# RoboticArmIEEE_Main.net
KiCad netlist of a schematic drawn in Altium Designer
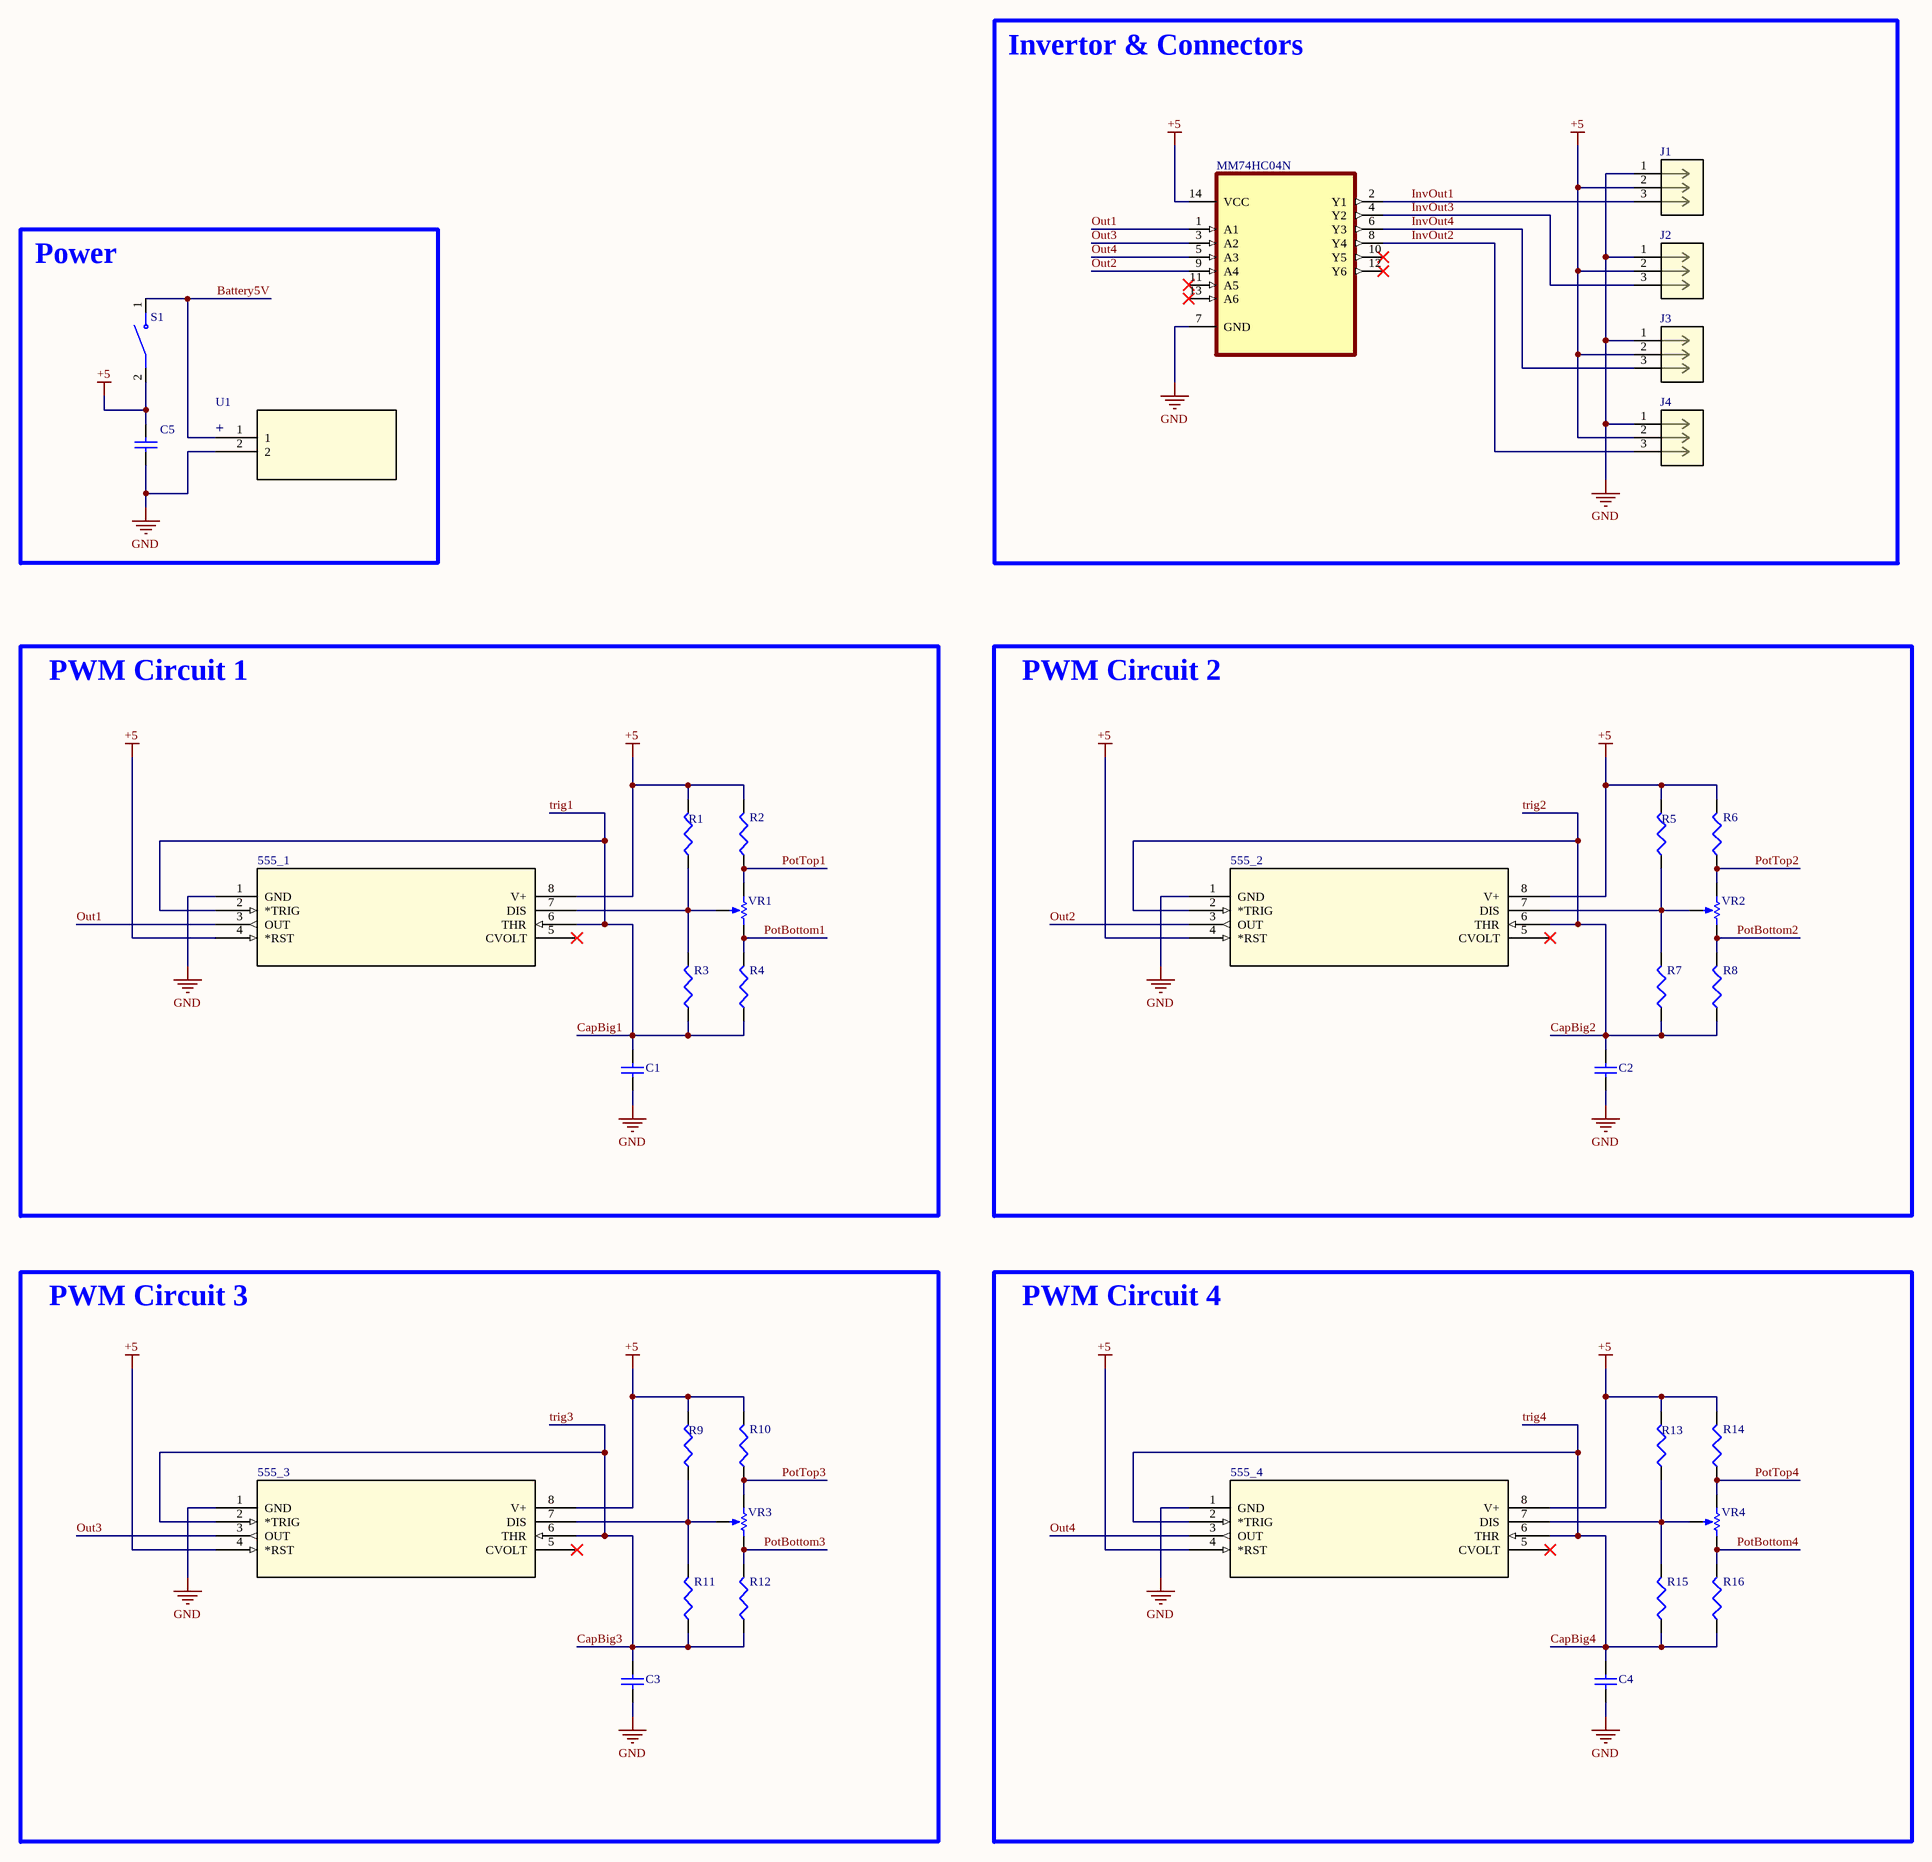
[diagram p0: RoboticArmIEEE_Main.SchDoc]

(export (version "E")
  (design (tool "Eeschema 10.0.6"))
  (components
    (comp (ref "555_1")
      (value "LMC555CNNOPB")
      (footprint "LMC555CNNOPB:N08E_TEX")
      (description "No Description Available")
      (libsource (lib "LMC555CNNOPB") (part "LMC555CNNOPB"))
    )
    (comp (ref "555_2")
      (value "LMC555CNNOPB")
      (footprint "LMC555CNNOPB:N08E_TEX")
      (description "No Description Available")
      (libsource (lib "LMC555CNNOPB") (part "LMC555CNNOPB"))
    )
    (comp (ref "555_3")
      (value "LMC555CNNOPB")
      (footprint "LMC555CNNOPB:N08E_TEX")
      (description "No Description Available")
      (libsource (lib "LMC555CNNOPB") (part "LMC555CNNOPB"))
    )
    (comp (ref "555_4")
      (value "LMC555CNNOPB")
      (footprint "LMC555CNNOPB:N08E_TEX")
      (description "No Description Available")
      (libsource (lib "LMC555CNNOPB") (part "LMC555CNNOPB"))
    )
    (comp (ref "C1")
      (value "Cap_Big")
      (footprint "Cap_Big")
      (libsource (lib "RoboticArmIEEE_SCHLib") (part "Cap_Big"))
    )
    (comp (ref "C2")
      (value "Cap_Big")
      (footprint "Cap_Big")
      (libsource (lib "RoboticArmIEEE_SCHLib") (part "Cap_Big"))
    )
    (comp (ref "C3")
      (value "Cap_Big")
      (footprint "Cap_Big")
      (libsource (lib "RoboticArmIEEE_SCHLib") (part "Cap_Big"))
    )
    (comp (ref "C4")
      (value "Cap_Big")
      (footprint "Cap_Big")
      (libsource (lib "RoboticArmIEEE_SCHLib") (part "Cap_Big"))
    )
    (comp (ref "C5")
      (value "Cap_Small")
      (footprint "RoboticArmIEEE_PCBLib:Cap_Small")
      (libsource (lib "RoboticArmIEEE_SCHLib") (part "Cap_Small"))
    )
    (comp (ref "J1")
      (value "PPTC031LFBN-RC")
      (footprint "PPTC031LFBN-RC:CONN_PPTC031_SUL")
      (description "No Description Available")
      (libsource (lib "PPTC031LFBN-RC") (part "PPTC031LFBN-RC"))
    )
    (comp (ref "J2")
      (value "PPTC031LFBN-RC")
      (footprint "PPTC031LFBN-RC:CONN_PPTC031_SUL")
      (description "No Description Available")
      (libsource (lib "PPTC031LFBN-RC") (part "PPTC031LFBN-RC"))
    )
    (comp (ref "J3")
      (value "PPTC031LFBN-RC")
      (footprint "PPTC031LFBN-RC:CONN_PPTC031_SUL")
      (description "No Description Available")
      (libsource (lib "PPTC031LFBN-RC") (part "PPTC031LFBN-RC"))
    )
    (comp (ref "J4")
      (value "PPTC031LFBN-RC")
      (footprint "PPTC031LFBN-RC:CONN_PPTC031_SUL")
      (description "No Description Available")
      (libsource (lib "PPTC031LFBN-RC") (part "PPTC031LFBN-RC"))
    )
    (comp (ref "MM74HC04N")
      (value "MM74HC04N")
      (footprint "DIP254P762X533-14")
      (description "Inverter IC 6 Channel 14-PDIP")
      (fields (field (name "MF") "ON Semiconductor"))
      (libsource (lib "Leon Engle") (part "MM74HC04N"))
    )
    (comp (ref "R1")
      (value "R?")
      (footprint "Resistor")
      (libsource (lib "RoboticArmIEEE_SCHLib") (part "Resistor"))
    )
    (comp (ref "R2")
      (value "Resistor")
      (footprint "Resistor")
      (libsource (lib "RoboticArmIEEE_SCHLib") (part "Resistor"))
    )
    (comp (ref "R3")
      (value "Resistor")
      (footprint "Resistor")
      (libsource (lib "RoboticArmIEEE_SCHLib") (part "Resistor"))
    )
    (comp (ref "R4")
      (value "Resistor")
      (footprint "Resistor")
      (libsource (lib "RoboticArmIEEE_SCHLib") (part "Resistor"))
    )
    (comp (ref "R5")
      (value "R?")
      (footprint "Resistor")
      (libsource (lib "RoboticArmIEEE_SCHLib") (part "Resistor"))
    )
    (comp (ref "R6")
      (value "Resistor")
      (footprint "Resistor")
      (libsource (lib "RoboticArmIEEE_SCHLib") (part "Resistor"))
    )
    (comp (ref "R7")
      (value "Resistor")
      (footprint "Resistor")
      (libsource (lib "RoboticArmIEEE_SCHLib") (part "Resistor"))
    )
    (comp (ref "R8")
      (value "Resistor")
      (footprint "Resistor")
      (libsource (lib "RoboticArmIEEE_SCHLib") (part "Resistor"))
    )
    (comp (ref "R9")
      (value "R?")
      (footprint "Resistor")
      (libsource (lib "RoboticArmIEEE_SCHLib") (part "Resistor"))
    )
    (comp (ref "R10")
      (value "Resistor")
      (footprint "Resistor")
      (libsource (lib "RoboticArmIEEE_SCHLib") (part "Resistor"))
    )
    (comp (ref "R11")
      (value "Resistor")
      (footprint "Resistor")
      (libsource (lib "RoboticArmIEEE_SCHLib") (part "Resistor"))
    )
    (comp (ref "R12")
      (value "Resistor")
      (footprint "Resistor")
      (libsource (lib "RoboticArmIEEE_SCHLib") (part "Resistor"))
    )
    (comp (ref "R13")
      (value "R?")
      (footprint "Resistor")
      (libsource (lib "RoboticArmIEEE_SCHLib") (part "Resistor"))
    )
    (comp (ref "R14")
      (value "Resistor")
      (footprint "Resistor")
      (libsource (lib "RoboticArmIEEE_SCHLib") (part "Resistor"))
    )
    (comp (ref "R15")
      (value "Resistor")
      (footprint "Resistor")
      (libsource (lib "RoboticArmIEEE_SCHLib") (part "Resistor"))
    )
    (comp (ref "R16")
      (value "Resistor")
      (footprint "Resistor")
      (libsource (lib "RoboticArmIEEE_SCHLib") (part "Resistor"))
    )
    (comp (ref "S1")
      (value "GF-123-0054")
      (footprint "SW_GF-123-0054:SW_GF-123-0054")
      (description "Slide Switch SPST Through Hole")
      (libsource (lib "GF-123-0054") (part "GF-123-0054"))
    )
    (comp (ref "U1")
      (value "2479")
      (footprint "2479:2479PCB_37P49X52P63_KEY")
      (description "No Description Available")
      (libsource (lib "2479") (part "2479"))
    )
    (comp (ref "VR1")
      (value "P160KNPD-2QC25B2K")
      (footprint "P160KNPD-2QC25B2K:IC3_P160KNPD-2QC25B2K_BIT")
      (description "No Description Available")
      (libsource (lib "P160KNPD-2QC25B2K") (part "P160KNPD-2QC25B2K"))
    )
    (comp (ref "VR2")
      (value "P160KNPD-2QC25B2K")
      (footprint "P160KNPD-2QC25B2K:IC3_P160KNPD-2QC25B2K_BIT")
      (description "No Description Available")
      (libsource (lib "P160KNPD-2QC25B2K") (part "P160KNPD-2QC25B2K"))
    )
    (comp (ref "VR3")
      (value "P160KNPD-2QC25B2K")
      (footprint "P160KNPD-2QC25B2K:IC3_P160KNPD-2QC25B2K_BIT")
      (description "No Description Available")
      (libsource (lib "P160KNPD-2QC25B2K") (part "P160KNPD-2QC25B2K"))
    )
    (comp (ref "VR4")
      (value "P160KNPD-2QC25B2K")
      (footprint "P160KNPD-2QC25B2K:IC3_P160KNPD-2QC25B2K_BIT")
      (description "No Description Available")
      (libsource (lib "P160KNPD-2QC25B2K") (part "P160KNPD-2QC25B2K"))
    )
  )
  (nets
    (net (code "1") (name "+5") (class "Default")
      (node (ref "555_1") (pin "4") (pinfunction "*RST_4") (pintype "input"))
      (node (ref "555_1") (pin "8") (pinfunction "V+_8") (pintype "power_in"))
      (node (ref "555_2") (pin "4") (pinfunction "*RST_4") (pintype "input"))
      (node (ref "555_2") (pin "8") (pinfunction "V+_8") (pintype "power_in"))
      (node (ref "555_3") (pin "4") (pinfunction "*RST_4") (pintype "input"))
      (node (ref "555_3") (pin "8") (pinfunction "V+_8") (pintype "power_in"))
      (node (ref "555_4") (pin "4") (pinfunction "*RST_4") (pintype "input"))
      (node (ref "555_4") (pin "8") (pinfunction "V+_8") (pintype "power_in"))
      (node (ref "C5") (pin "2") (pinfunction "2_2") (pintype "passive"))
      (node (ref "J1") (pin "2") (pinfunction "2_2") (pintype "passive"))
      (node (ref "J2") (pin "2") (pinfunction "2_2") (pintype "passive"))
      (node (ref "J3") (pin "2") (pinfunction "2_2") (pintype "passive"))
      (node (ref "J4") (pin "2") (pinfunction "2_2") (pintype "passive"))
      (node (ref "MM74HC04N") (pin "14") (pinfunction "VCC_14") (pintype "power_in"))
      (node (ref "R1") (pin "2") (pinfunction "2_2") (pintype "passive"))
      (node (ref "R10") (pin "2") (pinfunction "2_2") (pintype "passive"))
      (node (ref "R13") (pin "2") (pinfunction "2_2") (pintype "passive"))
      (node (ref "R14") (pin "2") (pinfunction "2_2") (pintype "passive"))
      (node (ref "R2") (pin "2") (pinfunction "2_2") (pintype "passive"))
      (node (ref "R5") (pin "2") (pinfunction "2_2") (pintype "passive"))
      (node (ref "R6") (pin "2") (pinfunction "2_2") (pintype "passive"))
      (node (ref "R9") (pin "2") (pinfunction "2_2") (pintype "passive"))
      (node (ref "S1") (pin "2") (pinfunction "2_2") (pintype "passive"))
    )
    (net (code "2") (name "/Battery5V") (class "Default")
      (node (ref "S1") (pin "1") (pinfunction "1_1") (pintype "passive"))
      (node (ref "U1") (pin "1") (pinfunction "1_1") (pintype "passive"))
    )
    (net (code "3") (name "/CapBig1") (class "Default")
      (node (ref "555_1") (pin "2") (pinfunction "*TRIG_2") (pintype "input"))
      (node (ref "555_1") (pin "6") (pinfunction "THR_6") (pintype "input"))
      (node (ref "C1") (pin "2") (pinfunction "2_2") (pintype "passive"))
      (node (ref "R3") (pin "1") (pinfunction "1_1") (pintype "passive"))
      (node (ref "R4") (pin "1") (pinfunction "1_1") (pintype "passive"))
    )
    (net (code "4") (name "/CapBig2") (class "Default")
      (node (ref "555_2") (pin "2") (pinfunction "*TRIG_2") (pintype "input"))
      (node (ref "555_2") (pin "6") (pinfunction "THR_6") (pintype "input"))
      (node (ref "C2") (pin "2") (pinfunction "2_2") (pintype "passive"))
      (node (ref "R7") (pin "1") (pinfunction "1_1") (pintype "passive"))
      (node (ref "R8") (pin "1") (pinfunction "1_1") (pintype "passive"))
    )
    (net (code "5") (name "/CapBig3") (class "Default")
      (node (ref "555_3") (pin "2") (pinfunction "*TRIG_2") (pintype "input"))
      (node (ref "555_3") (pin "6") (pinfunction "THR_6") (pintype "input"))
      (node (ref "C3") (pin "2") (pinfunction "2_2") (pintype "passive"))
      (node (ref "R11") (pin "1") (pinfunction "1_1") (pintype "passive"))
      (node (ref "R12") (pin "1") (pinfunction "1_1") (pintype "passive"))
    )
    (net (code "6") (name "/CapBig4") (class "Default")
      (node (ref "555_4") (pin "2") (pinfunction "*TRIG_2") (pintype "input"))
      (node (ref "555_4") (pin "6") (pinfunction "THR_6") (pintype "input"))
      (node (ref "C4") (pin "2") (pinfunction "2_2") (pintype "passive"))
      (node (ref "R15") (pin "1") (pinfunction "1_1") (pintype "passive"))
      (node (ref "R16") (pin "1") (pinfunction "1_1") (pintype "passive"))
    )
    (net (code "7") (name "/InvOut1") (class "Default")
      (node (ref "J1") (pin "3") (pinfunction "3_3") (pintype "passive"))
      (node (ref "MM74HC04N") (pin "2") (pinfunction "Y1_2") (pintype "output"))
    )
    (net (code "8") (name "/InvOut2") (class "Default")
      (node (ref "J4") (pin "3") (pinfunction "3_3") (pintype "passive"))
      (node (ref "MM74HC04N") (pin "8") (pinfunction "Y4_8") (pintype "output"))
    )
    (net (code "9") (name "/InvOut3") (class "Default")
      (node (ref "J2") (pin "3") (pinfunction "3_3") (pintype "passive"))
      (node (ref "MM74HC04N") (pin "4") (pinfunction "Y2_4") (pintype "output"))
    )
    (net (code "10") (name "/InvOut4") (class "Default")
      (node (ref "J3") (pin "3") (pinfunction "3_3") (pintype "passive"))
      (node (ref "MM74HC04N") (pin "6") (pinfunction "Y3_6") (pintype "output"))
    )
    (net (code "11") (name "/Out1") (class "Default")
      (node (ref "555_1") (pin "3") (pinfunction "OUT_3") (pintype "output"))
      (node (ref "MM74HC04N") (pin "1") (pinfunction "A1_1") (pintype "input"))
    )
    (net (code "12") (name "/Out2") (class "Default")
      (node (ref "555_2") (pin "3") (pinfunction "OUT_3") (pintype "output"))
      (node (ref "MM74HC04N") (pin "9") (pinfunction "A4_9") (pintype "input"))
    )
    (net (code "13") (name "/Out3") (class "Default")
      (node (ref "555_3") (pin "3") (pinfunction "OUT_3") (pintype "output"))
      (node (ref "MM74HC04N") (pin "3") (pinfunction "A2_3") (pintype "input"))
    )
    (net (code "14") (name "/Out4") (class "Default")
      (node (ref "555_4") (pin "3") (pinfunction "OUT_3") (pintype "output"))
      (node (ref "MM74HC04N") (pin "5") (pinfunction "A3_5") (pintype "input"))
    )
    (net (code "15") (name "/PotBottom1") (class "Default")
      (node (ref "R4") (pin "2") (pinfunction "2_2") (pintype "passive"))
      (node (ref "VR1") (pin "1") (pinfunction "CW_1") (pintype "passive"))
    )
    (net (code "16") (name "/PotBottom2") (class "Default")
      (node (ref "R8") (pin "2") (pinfunction "2_2") (pintype "passive"))
      (node (ref "VR2") (pin "1") (pinfunction "CW_1") (pintype "passive"))
    )
    (net (code "17") (name "/PotBottom3") (class "Default")
      (node (ref "R12") (pin "2") (pinfunction "2_2") (pintype "passive"))
      (node (ref "VR3") (pin "1") (pinfunction "CW_1") (pintype "passive"))
    )
    (net (code "18") (name "/PotBottom4") (class "Default")
      (node (ref "R16") (pin "2") (pinfunction "2_2") (pintype "passive"))
      (node (ref "VR4") (pin "1") (pinfunction "CW_1") (pintype "passive"))
    )
    (net (code "19") (name "/PotTop1") (class "Default")
      (node (ref "R2") (pin "1") (pinfunction "1_1") (pintype "passive"))
      (node (ref "VR1") (pin "3") (pinfunction "CCW_3") (pintype "passive"))
    )
    (net (code "20") (name "/PotTop2") (class "Default")
      (node (ref "R6") (pin "1") (pinfunction "1_1") (pintype "passive"))
      (node (ref "VR2") (pin "3") (pinfunction "CCW_3") (pintype "passive"))
    )
    (net (code "21") (name "/PotTop3") (class "Default")
      (node (ref "R10") (pin "1") (pinfunction "1_1") (pintype "passive"))
      (node (ref "VR3") (pin "3") (pinfunction "CCW_3") (pintype "passive"))
    )
    (net (code "22") (name "/PotTop4") (class "Default")
      (node (ref "R14") (pin "1") (pinfunction "1_1") (pintype "passive"))
      (node (ref "VR4") (pin "3") (pinfunction "CCW_3") (pintype "passive"))
    )
    (net (code "23") (name "GND") (class "Default")
      (node (ref "555_1") (pin "1") (pinfunction "GND_1") (pintype "power_in"))
      (node (ref "555_2") (pin "1") (pinfunction "GND_1") (pintype "power_in"))
      (node (ref "555_3") (pin "1") (pinfunction "GND_1") (pintype "power_in"))
      (node (ref "555_4") (pin "1") (pinfunction "GND_1") (pintype "power_in"))
      (node (ref "C1") (pin "1") (pinfunction "1_1") (pintype "passive"))
      (node (ref "C2") (pin "1") (pinfunction "1_1") (pintype "passive"))
      (node (ref "C3") (pin "1") (pinfunction "1_1") (pintype "passive"))
      (node (ref "C4") (pin "1") (pinfunction "1_1") (pintype "passive"))
      (node (ref "C5") (pin "1") (pinfunction "1_1") (pintype "passive"))
      (node (ref "J1") (pin "1") (pinfunction "1_1") (pintype "passive"))
      (node (ref "J2") (pin "1") (pinfunction "1_1") (pintype "passive"))
      (node (ref "J3") (pin "1") (pinfunction "1_1") (pintype "passive"))
      (node (ref "J4") (pin "1") (pinfunction "1_1") (pintype "passive"))
      (node (ref "MM74HC04N") (pin "7") (pinfunction "GND_7") (pintype "passive"))
      (node (ref "U1") (pin "2") (pinfunction "2_2") (pintype "passive"))
    )
    (net (code "24") (name "Net-(555_1-DIS)") (class "Default")
      (node (ref "555_1") (pin "7") (pinfunction "DIS_7") (pintype "passive"))
      (node (ref "R1") (pin "1") (pinfunction "1_1") (pintype "passive"))
      (node (ref "R3") (pin "2") (pinfunction "2_2") (pintype "passive"))
      (node (ref "VR1") (pin "2") (pinfunction "S_2") (pintype "passive"))
    )
    (net (code "25") (name "Net-(555_2-DIS)") (class "Default")
      (node (ref "555_2") (pin "7") (pinfunction "DIS_7") (pintype "passive"))
      (node (ref "R5") (pin "1") (pinfunction "1_1") (pintype "passive"))
      (node (ref "R7") (pin "2") (pinfunction "2_2") (pintype "passive"))
      (node (ref "VR2") (pin "2") (pinfunction "S_2") (pintype "passive"))
    )
    (net (code "26") (name "Net-(555_3-DIS)") (class "Default")
      (node (ref "555_3") (pin "7") (pinfunction "DIS_7") (pintype "passive"))
      (node (ref "R11") (pin "2") (pinfunction "2_2") (pintype "passive"))
      (node (ref "R9") (pin "1") (pinfunction "1_1") (pintype "passive"))
      (node (ref "VR3") (pin "2") (pinfunction "S_2") (pintype "passive"))
    )
    (net (code "27") (name "Net-(555_4-DIS)") (class "Default")
      (node (ref "555_4") (pin "7") (pinfunction "DIS_7") (pintype "passive"))
      (node (ref "R13") (pin "1") (pinfunction "1_1") (pintype "passive"))
      (node (ref "R15") (pin "2") (pinfunction "2_2") (pintype "passive"))
      (node (ref "VR4") (pin "2") (pinfunction "S_2") (pintype "passive"))
    )
    (net (code "28") (name "unconnected-(555_1-CVOLT-Pad5)") (class "Default")
      (node (ref "555_1") (pin "5") (pinfunction "CVOLT_5") (pintype "passive+no_connect"))
    )
    (net (code "29") (name "unconnected-(555_2-CVOLT-Pad5)") (class "Default")
      (node (ref "555_2") (pin "5") (pinfunction "CVOLT_5") (pintype "passive+no_connect"))
    )
    (net (code "30") (name "unconnected-(555_3-CVOLT-Pad5)") (class "Default")
      (node (ref "555_3") (pin "5") (pinfunction "CVOLT_5") (pintype "passive+no_connect"))
    )
    (net (code "31") (name "unconnected-(555_4-CVOLT-Pad5)") (class "Default")
      (node (ref "555_4") (pin "5") (pinfunction "CVOLT_5") (pintype "passive+no_connect"))
    )
    (net (code "32") (name "unconnected-(MM74HC04N-A5-Pad11)") (class "Default")
      (node (ref "MM74HC04N") (pin "11") (pinfunction "A5_11") (pintype "input+no_connect"))
    )
    (net (code "33") (name "unconnected-(MM74HC04N-A6-Pad13)") (class "Default")
      (node (ref "MM74HC04N") (pin "13") (pinfunction "A6_13") (pintype "input+no_connect"))
    )
    (net (code "34") (name "unconnected-(MM74HC04N-Y5-Pad10)") (class "Default")
      (node (ref "MM74HC04N") (pin "10") (pinfunction "Y5_10") (pintype "output+no_connect"))
    )
    (net (code "35") (name "unconnected-(MM74HC04N-Y6-Pad12)") (class "Default")
      (node (ref "MM74HC04N") (pin "12") (pinfunction "Y6_12") (pintype "output+no_connect"))
    )
  )
)
